# STM32F4.net
KiCad netlist of a schematic drawn in Altium Designer
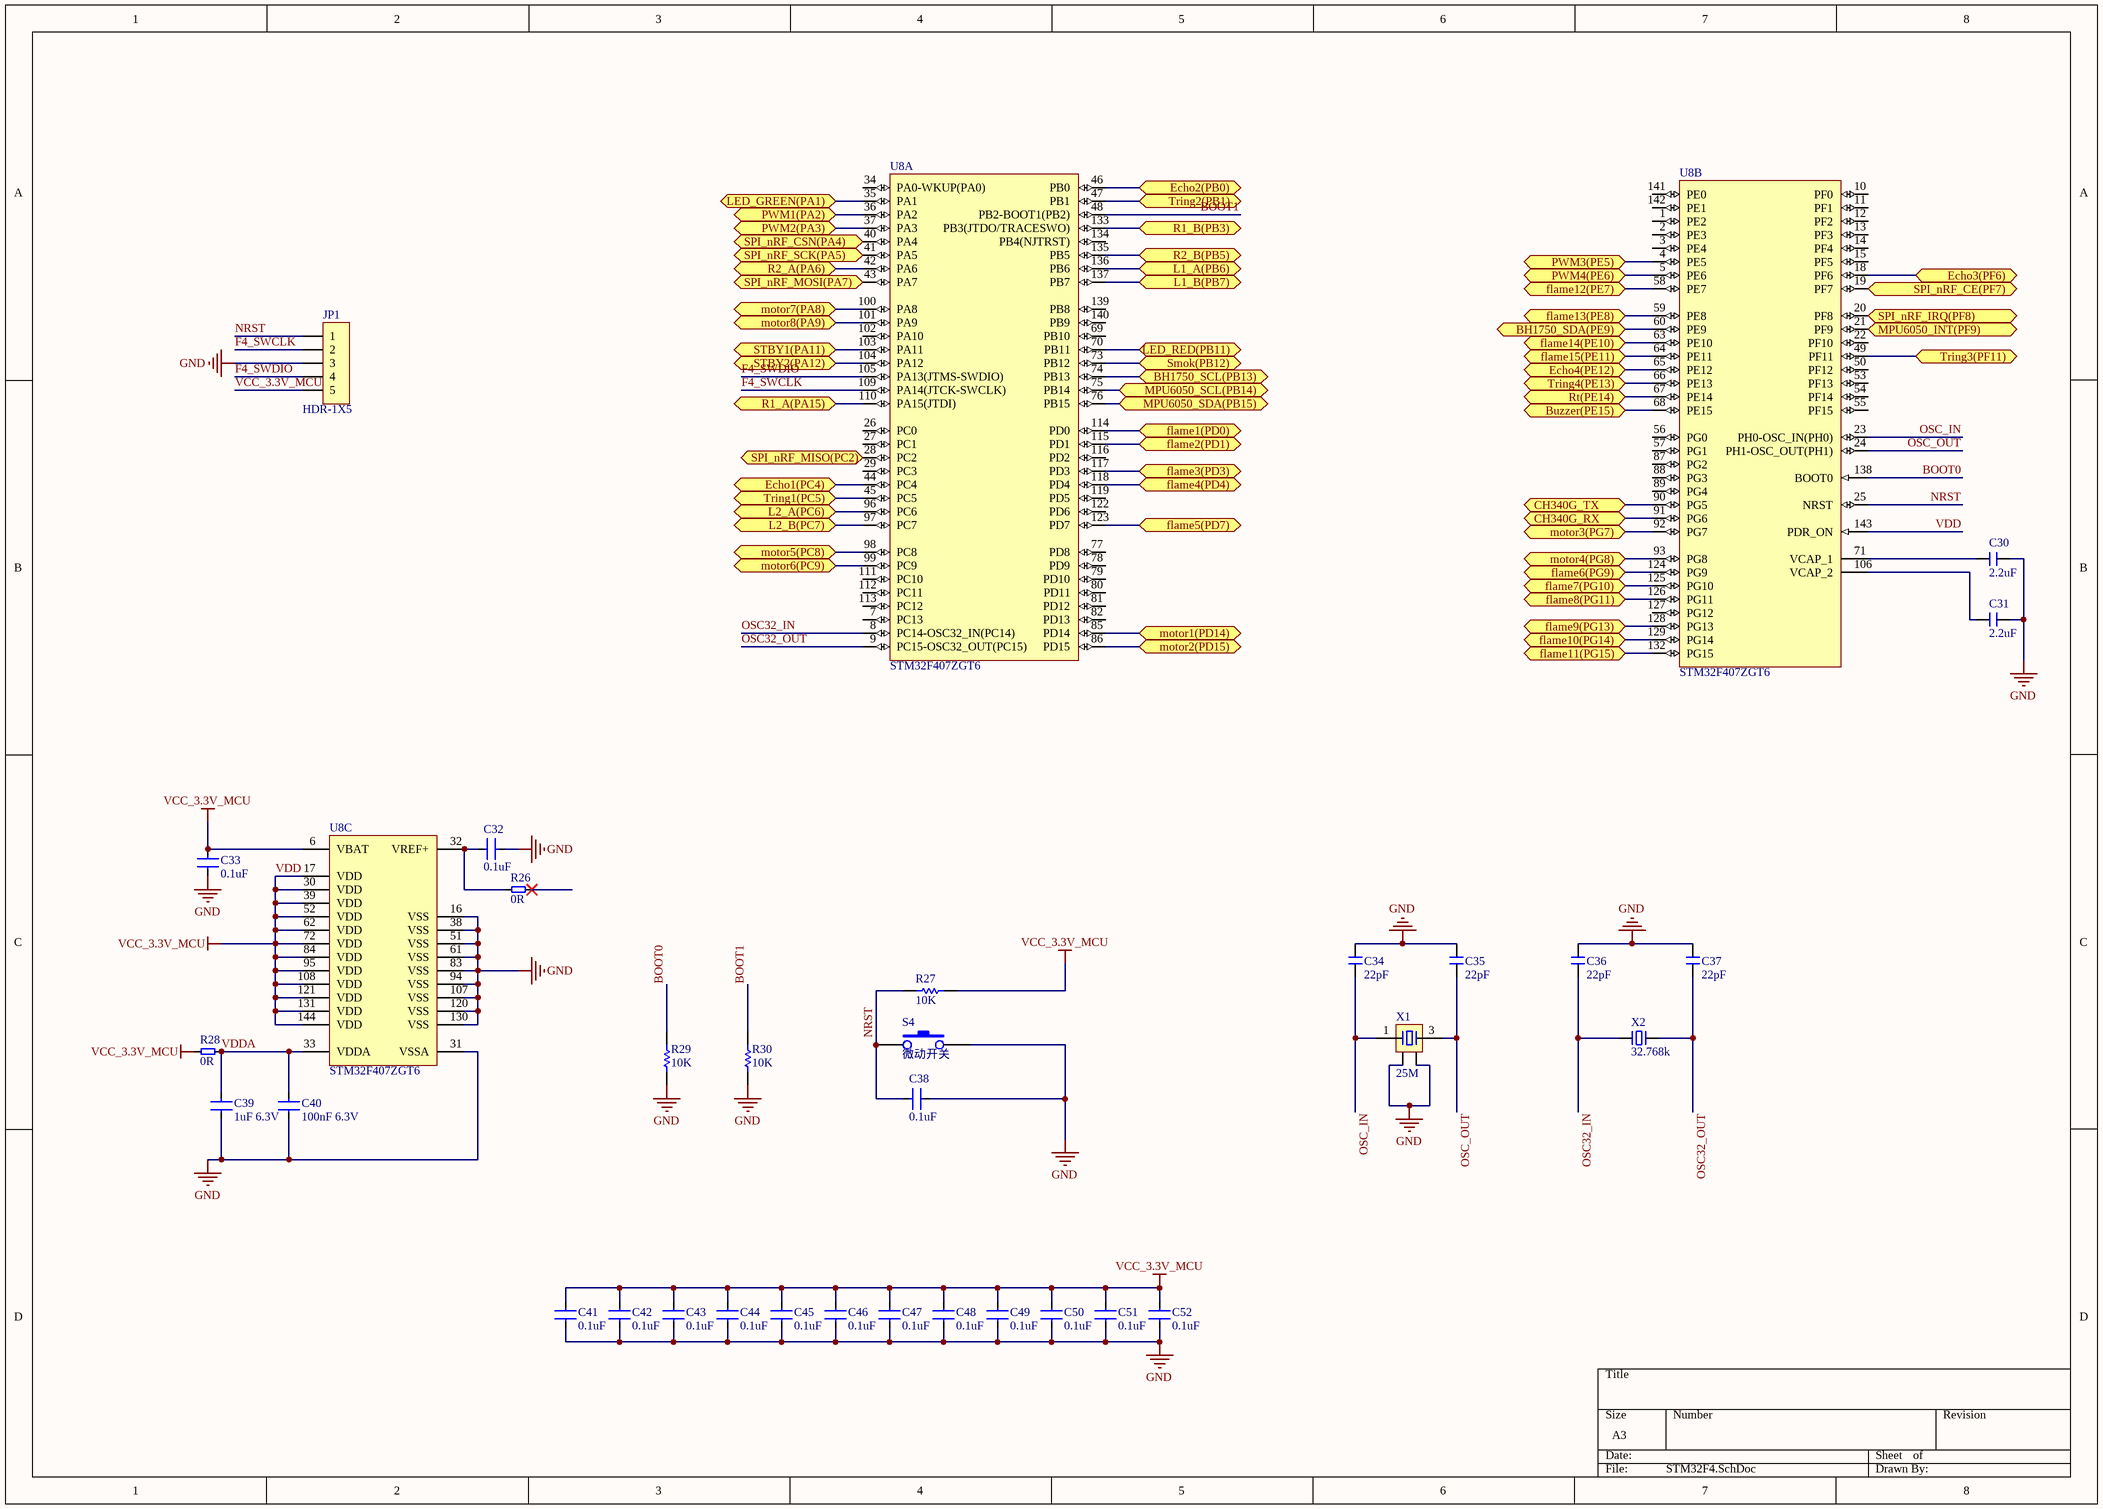
[diagram p0: STM32F4.SchDoc]

(export (version "E")
  (design (tool "Eeschema 10.0.6"))
  (components
    (comp (ref "C30")
      (value "2.2uF")
      (footprint "0603_C")
      (description "无极性贴片电容")
      (libsource (lib "3.1   - 电阻-电容-电感") (part "C"))
    )
    (comp (ref "C31")
      (value "2.2uF")
      (footprint "0603_C")
      (description "无极性贴片电容")
      (libsource (lib "3.1   - 电阻-电容-电感") (part "C"))
    )
    (comp (ref "C32") (value "0.1uF") (footprint "0603_C") (libsource (lib "电容") (part "C0805")))
    (comp (ref "C33") (value "0.1uF") (footprint "0603_C") (libsource (lib "电容") (part "C0805")))
    (comp (ref "C34")
      (value "22pF")
      (footprint "0603_C")
      (description "无极性贴片电容")
      (libsource (lib "3.1   - 电阻-电容-电感") (part "C"))
    )
    (comp (ref "C35")
      (value "22pF")
      (footprint "0603_C")
      (description "无极性贴片电容")
      (libsource (lib "3.1   - 电阻-电容-电感") (part "C"))
    )
    (comp (ref "C36")
      (value "22pF")
      (footprint "0603_C")
      (description "无极性贴片电容")
      (libsource (lib "3.1   - 电阻-电容-电感") (part "C"))
    )
    (comp (ref "C37")
      (value "22pF")
      (footprint "0603_C")
      (description "无极性贴片电容")
      (libsource (lib "3.1   - 电阻-电容-电感") (part "C"))
    )
    (comp (ref "C38") (value "0.1uF") (footprint "0603_C") (libsource (lib "电容") (part "C0805")))
    (comp (ref "C39") (value "1uF 6.3V") (footprint "0603_C") (libsource (lib "电容") (part "C0805")))
    (comp (ref "C40") (value "100nF 6.3V") (footprint "0603_C") (libsource (lib "电容") (part "C0805")))
    (comp (ref "C41") (value "0.1uF") (footprint "0603_C") (libsource (lib "电容") (part "C0805")))
    (comp (ref "C42") (value "0.1uF") (footprint "0603_C") (libsource (lib "电容") (part "C0805")))
    (comp (ref "C43") (value "0.1uF") (footprint "0603_C") (libsource (lib "电容") (part "C0805")))
    (comp (ref "C44") (value "0.1uF") (footprint "0603_C") (libsource (lib "电容") (part "C0805")))
    (comp (ref "C45") (value "0.1uF") (footprint "0603_C") (libsource (lib "电容") (part "C0805")))
    (comp (ref "C46") (value "0.1uF") (footprint "0603_C") (libsource (lib "电容") (part "C0805")))
    (comp (ref "C47") (value "0.1uF") (footprint "0603_C") (libsource (lib "电容") (part "C0805")))
    (comp (ref "C48") (value "0.1uF") (footprint "0603_C") (libsource (lib "电容") (part "C0805")))
    (comp (ref "C49") (value "0.1uF") (footprint "0603_C") (libsource (lib "电容") (part "C0805")))
    (comp (ref "C50") (value "0.1uF") (footprint "0603_C") (libsource (lib "电容") (part "C0805")))
    (comp (ref "C51") (value "0.1uF") (footprint "0603_C") (libsource (lib "电容") (part "C0805")))
    (comp (ref "C52") (value "0.1uF") (footprint "0603_C") (libsource (lib "电容") (part "C0805")))
    (comp (ref "JP1")
      (value "HDR-1X5")
      (footprint "XH2.54-WI-5P")
      (description "5P接插件")
      (libsource (lib "4.5   - 接插件-脚距2.54") (part "Header 5"))
    )
    (comp (ref "R26") (value "0R") (footprint "0603_L") (libsource (lib "电阻") (part "R0805")))
    (comp (ref "R27")
      (value "10K")
      (footprint "0603_R")
      (description "Resistor")
      (libsource (lib "Miscellaneous Devices") (part "Res1"))
    )
    (comp (ref "R28") (value "0R") (footprint "0603_L") (libsource (lib "电阻") (part "R0805")))
    (comp (ref "R29")
      (value "10K")
      (footprint "0603_R")
      (description "Resistor")
      (libsource (lib "Miscellaneous Devices") (part "Res1"))
    )
    (comp (ref "R30")
      (value "10K")
      (footprint "0603_R")
      (description "Resistor")
      (libsource (lib "Miscellaneous Devices") (part "Res1"))
    )
    (comp (ref "S4") (value "微动开关") (footprint "微动开关-1") (libsource (lib "开关") (part "微动开关")))
    (comp (ref "U8")
      (value "STM32F407ZGT6")
      (footprint "STM-LQFP144_N")
      (fields (field (name "MANUFACTURER") "STMicroelectronics"))
      (libsource (lib "STMicroelectronics STM32 F4") (part "STM32F407ZGT6"))
    )
    (comp (ref "X1")
      (value "25M")
      (footprint "SMD-3225_4P")
      (description "4脚无源晶振")
      (libsource (lib "10.1 - 保险丝-晶振") (part "XTAL-4P"))
    )
    (comp (ref "X2")
      (value "32.768k")
      (footprint "SMD-3215_2P FC - 135")
      (description "2脚无源脚晶振")
      (libsource (lib "10.1 - 保险丝-晶振") (part "XTAL-2P"))
    )
  )
  (nets
    (net (code "1") (name "/BH1750_SCL(PB13)") (class "Default")
      (node (ref "U8") (pin "74") (pinfunction "PB13_74") (pintype "bidirectional"))
    )
    (net (code "2") (name "/BH1750_SDA(PE9)") (class "Default")
      (node (ref "U8") (pin "60") (pinfunction "PE9_60") (pintype "bidirectional"))
    )
    (net (code "3") (name "/BOOT0") (class "Default")
      (node (ref "R29") (pin "1") (pinfunction "1_1") (pintype "passive"))
      (node (ref "U8") (pin "138") (pinfunction "BOOT0_138") (pintype "input"))
    )
    (net (code "4") (name "/BOOT1") (class "Default")
      (node (ref "R30") (pin "1") (pinfunction "1_1") (pintype "passive"))
      (node (ref "U8") (pin "48") (pinfunction "PB2-BOOT1(PB2)_48") (pintype "bidirectional"))
    )
    (net (code "5") (name "/Buzzer(PE15)") (class "Default")
      (node (ref "U8") (pin "68") (pinfunction "PE15_68") (pintype "bidirectional"))
    )
    (net (code "6") (name "/CH340G_RX") (class "Default")
      (node (ref "U8") (pin "91") (pinfunction "PG6_91") (pintype "bidirectional"))
    )
    (net (code "7") (name "/CH340G_TX") (class "Default")
      (node (ref "U8") (pin "90") (pinfunction "PG5_90") (pintype "bidirectional"))
    )
    (net (code "8") (name "/Echo1(PC4)") (class "Default")
      (node (ref "U8") (pin "44") (pinfunction "PC4_44") (pintype "bidirectional"))
    )
    (net (code "9") (name "/Echo2(PB0)") (class "Default")
      (node (ref "U8") (pin "46") (pinfunction "PB0_46") (pintype "bidirectional"))
    )
    (net (code "10") (name "/Echo3(PF6)") (class "Default")
      (node (ref "U8") (pin "18") (pinfunction "PF6_18") (pintype "bidirectional"))
    )
    (net (code "11") (name "/Echo4(PE12)") (class "Default")
      (node (ref "U8") (pin "65") (pinfunction "PE12_65") (pintype "bidirectional"))
    )
    (net (code "12") (name "/F4_SWCLK") (class "Default")
      (node (ref "JP1") (pin "2") (pinfunction "2_2") (pintype "passive"))
      (node (ref "U8") (pin "109") (pinfunction "PA14(JTCK-SWCLK)_109") (pintype "bidirectional"))
    )
    (net (code "13") (name "/F4_SWDIO") (class "Default")
      (node (ref "JP1") (pin "4") (pinfunction "4_4") (pintype "passive"))
      (node (ref "U8") (pin "105") (pinfunction "PA13(JTMS-SWDIO)_105") (pintype "bidirectional"))
    )
    (net (code "14") (name "/L1_A(PB6)") (class "Default")
      (node (ref "U8") (pin "136") (pinfunction "PB6_136") (pintype "bidirectional"))
    )
    (net (code "15") (name "/L1_B(PB7)") (class "Default")
      (node (ref "U8") (pin "137") (pinfunction "PB7_137") (pintype "bidirectional"))
    )
    (net (code "16") (name "/L2_A(PC6)") (class "Default")
      (node (ref "U8") (pin "96") (pinfunction "PC6_96") (pintype "bidirectional"))
    )
    (net (code "17") (name "/L2_B(PC7)") (class "Default")
      (node (ref "U8") (pin "97") (pinfunction "PC7_97") (pintype "bidirectional"))
    )
    (net (code "18") (name "/LED_GREEN(PA1)") (class "Default")
      (node (ref "U8") (pin "35") (pinfunction "PA1_35") (pintype "bidirectional"))
    )
    (net (code "19") (name "/LED_RED(PB11)") (class "Default")
      (node (ref "U8") (pin "70") (pinfunction "PB11_70") (pintype "bidirectional"))
    )
    (net (code "20") (name "/MPU6050_INT(PF9)") (class "Default")
      (node (ref "U8") (pin "21") (pinfunction "PF9_21") (pintype "bidirectional"))
    )
    (net (code "21") (name "/MPU6050_SCL(PB14)") (class "Default")
      (node (ref "U8") (pin "75") (pinfunction "PB14_75") (pintype "bidirectional"))
    )
    (net (code "22") (name "/MPU6050_SDA(PB15)") (class "Default")
      (node (ref "U8") (pin "76") (pinfunction "PB15_76") (pintype "bidirectional"))
    )
    (net (code "23") (name "/NRST") (class "Default")
      (node (ref "C38") (pin "1") (pinfunction "1_1") (pintype "passive"))
      (node (ref "JP1") (pin "1") (pinfunction "1_1") (pintype "passive"))
      (node (ref "R27") (pin "1") (pinfunction "1_1") (pintype "passive"))
      (node (ref "S4") (pin "1") (pinfunction "1_1") (pintype "passive"))
      (node (ref "U8") (pin "25") (pinfunction "NRST_25") (pintype "bidirectional"))
    )
    (net (code "24") (name "/OSC32_IN") (class "Default")
      (node (ref "C36") (pin "2") (pinfunction "2_2") (pintype "passive"))
      (node (ref "U8") (pin "8") (pinfunction "PC14-OSC32_IN(PC14)_8") (pintype "bidirectional"))
      (node (ref "X2") (pin "1") (pinfunction "1_1") (pintype "passive"))
    )
    (net (code "25") (name "/OSC32_OUT") (class "Default")
      (node (ref "C37") (pin "2") (pinfunction "2_2") (pintype "passive"))
      (node (ref "U8") (pin "9") (pinfunction "PC15-OSC32_OUT(PC15)_9") (pintype "bidirectional"))
      (node (ref "X2") (pin "2") (pinfunction "2_2") (pintype "passive"))
    )
    (net (code "26") (name "/OSC_IN") (class "Default")
      (node (ref "C34") (pin "2") (pinfunction "2_2") (pintype "passive"))
      (node (ref "U8") (pin "23") (pinfunction "PH0-OSC_IN(PH0)_23") (pintype "bidirectional"))
      (node (ref "X1") (pin "1") (pinfunction "1_1") (pintype "passive"))
    )
    (net (code "27") (name "/OSC_OUT") (class "Default")
      (node (ref "C35") (pin "2") (pinfunction "2_2") (pintype "passive"))
      (node (ref "U8") (pin "24") (pinfunction "PH1-OSC_OUT(PH1)_24") (pintype "bidirectional"))
      (node (ref "X1") (pin "3") (pinfunction "3_3") (pintype "passive"))
    )
    (net (code "28") (name "/PWM1(PA2)") (class "Default")
      (node (ref "U8") (pin "36") (pinfunction "PA2_36") (pintype "bidirectional"))
    )
    (net (code "29") (name "/PWM2(PA3)") (class "Default")
      (node (ref "U8") (pin "37") (pinfunction "PA3_37") (pintype "bidirectional"))
    )
    (net (code "30") (name "/PWM3(PE5)") (class "Default")
      (node (ref "U8") (pin "4") (pinfunction "PE5_4") (pintype "bidirectional"))
    )
    (net (code "31") (name "/PWM4(PE6)") (class "Default")
      (node (ref "U8") (pin "5") (pinfunction "PE6_5") (pintype "bidirectional"))
    )
    (net (code "32") (name "/R1_A(PA15)") (class "Default")
      (node (ref "U8") (pin "110") (pinfunction "PA15(JTDI)_110") (pintype "bidirectional"))
    )
    (net (code "33") (name "/R1_B(PB3)") (class "Default")
      (node (ref "U8") (pin "133") (pinfunction "PB3(JTDO/TRACESWO)_133") (pintype "bidirectional"))
    )
    (net (code "34") (name "/R2_A(PA6)") (class "Default")
      (node (ref "U8") (pin "42") (pinfunction "PA6_42") (pintype "bidirectional"))
    )
    (net (code "35") (name "/R2_B(PB5)") (class "Default")
      (node (ref "U8") (pin "135") (pinfunction "PB5_135") (pintype "bidirectional"))
    )
    (net (code "36") (name "/Rt(PE14)") (class "Default")
      (node (ref "U8") (pin "67") (pinfunction "PE14_67") (pintype "bidirectional"))
    )
    (net (code "37") (name "/SPI_nRF_CE(PF7)") (class "Default")
      (node (ref "U8") (pin "19") (pinfunction "PF7_19") (pintype "bidirectional"))
    )
    (net (code "38") (name "/SPI_nRF_CSN(PA4)") (class "Default")
      (node (ref "U8") (pin "40") (pinfunction "PA4_40") (pintype "bidirectional"))
    )
    (net (code "39") (name "/SPI_nRF_IRQ(PF8)") (class "Default")
      (node (ref "U8") (pin "20") (pinfunction "PF8_20") (pintype "bidirectional"))
    )
    (net (code "40") (name "/SPI_nRF_MISO(PC2)") (class "Default")
      (node (ref "U8") (pin "28") (pinfunction "PC2_28") (pintype "bidirectional"))
    )
    (net (code "41") (name "/SPI_nRF_MOSI(PA7)") (class "Default")
      (node (ref "U8") (pin "43") (pinfunction "PA7_43") (pintype "bidirectional"))
    )
    (net (code "42") (name "/SPI_nRF_SCK(PA5)") (class "Default")
      (node (ref "U8") (pin "41") (pinfunction "PA5_41") (pintype "bidirectional"))
    )
    (net (code "43") (name "/STBY1(PA11)") (class "Default")
      (node (ref "U8") (pin "103") (pinfunction "PA11_103") (pintype "bidirectional"))
    )
    (net (code "44") (name "/STBY2(PA12)") (class "Default")
      (node (ref "U8") (pin "104") (pinfunction "PA12_104") (pintype "bidirectional"))
    )
    (net (code "45") (name "/Smok(PB12)") (class "Default")
      (node (ref "U8") (pin "73") (pinfunction "PB12_73") (pintype "bidirectional"))
    )
    (net (code "46") (name "/Tring1(PC5)") (class "Default")
      (node (ref "U8") (pin "45") (pinfunction "PC5_45") (pintype "bidirectional"))
    )
    (net (code "47") (name "/Tring2(PB1)") (class "Default")
      (node (ref "U8") (pin "47") (pinfunction "PB1_47") (pintype "bidirectional"))
    )
    (net (code "48") (name "/Tring3(PF11)") (class "Default")
      (node (ref "U8") (pin "49") (pinfunction "PF11_49") (pintype "bidirectional"))
    )
    (net (code "49") (name "/Tring4(PE13)") (class "Default")
      (node (ref "U8") (pin "66") (pinfunction "PE13_66") (pintype "bidirectional"))
    )
    (net (code "50") (name "/VDDA") (class "Default")
      (node (ref "C39") (pin "1") (pinfunction "1_1") (pintype "passive"))
      (node (ref "C40") (pin "1") (pinfunction "1_1") (pintype "passive"))
      (node (ref "R28") (pin "2") (pinfunction "2_2") (pintype "passive"))
      (node (ref "U8") (pin "33") (pinfunction "VDDA_33") (pintype "power_in"))
    )
    (net (code "51") (name "/flame1(PD0)") (class "Default")
      (node (ref "U8") (pin "114") (pinfunction "PD0_114") (pintype "bidirectional"))
    )
    (net (code "52") (name "/flame2(PD1)") (class "Default")
      (node (ref "U8") (pin "115") (pinfunction "PD1_115") (pintype "bidirectional"))
    )
    (net (code "53") (name "/flame3(PD3)") (class "Default")
      (node (ref "U8") (pin "117") (pinfunction "PD3_117") (pintype "bidirectional"))
    )
    (net (code "54") (name "/flame4(PD4)") (class "Default")
      (node (ref "U8") (pin "118") (pinfunction "PD4_118") (pintype "bidirectional"))
    )
    (net (code "55") (name "/flame5(PD7)") (class "Default")
      (node (ref "U8") (pin "123") (pinfunction "PD7_123") (pintype "bidirectional"))
    )
    (net (code "56") (name "/flame6(PG9)") (class "Default")
      (node (ref "U8") (pin "124") (pinfunction "PG9_124") (pintype "bidirectional"))
    )
    (net (code "57") (name "/flame7(PG10)") (class "Default")
      (node (ref "U8") (pin "125") (pinfunction "PG10_125") (pintype "bidirectional"))
    )
    (net (code "58") (name "/flame8(PG11)") (class "Default")
      (node (ref "U8") (pin "126") (pinfunction "PG11_126") (pintype "bidirectional"))
    )
    (net (code "59") (name "/flame9(PG13)") (class "Default")
      (node (ref "U8") (pin "128") (pinfunction "PG13_128") (pintype "bidirectional"))
    )
    (net (code "60") (name "/flame10(PG14)") (class "Default")
      (node (ref "U8") (pin "129") (pinfunction "PG14_129") (pintype "bidirectional"))
    )
    (net (code "61") (name "/flame11(PG15)") (class "Default")
      (node (ref "U8") (pin "132") (pinfunction "PG15_132") (pintype "bidirectional"))
    )
    (net (code "62") (name "/flame12(PE7)") (class "Default")
      (node (ref "U8") (pin "58") (pinfunction "PE7_58") (pintype "bidirectional"))
    )
    (net (code "63") (name "/flame13(PE8)") (class "Default")
      (node (ref "U8") (pin "59") (pinfunction "PE8_59") (pintype "bidirectional"))
    )
    (net (code "64") (name "/flame14(PE10)") (class "Default")
      (node (ref "U8") (pin "63") (pinfunction "PE10_63") (pintype "bidirectional"))
    )
    (net (code "65") (name "/flame15(PE11)") (class "Default")
      (node (ref "U8") (pin "64") (pinfunction "PE11_64") (pintype "bidirectional"))
    )
    (net (code "66") (name "/motor1(PD14)") (class "Default")
      (node (ref "U8") (pin "85") (pinfunction "PD14_85") (pintype "bidirectional"))
    )
    (net (code "67") (name "/motor2(PD15)") (class "Default")
      (node (ref "U8") (pin "86") (pinfunction "PD15_86") (pintype "bidirectional"))
    )
    (net (code "68") (name "/motor3(PG7)") (class "Default")
      (node (ref "U8") (pin "92") (pinfunction "PG7_92") (pintype "bidirectional"))
    )
    (net (code "69") (name "/motor4(PG8)") (class "Default")
      (node (ref "U8") (pin "93") (pinfunction "PG8_93") (pintype "bidirectional"))
    )
    (net (code "70") (name "/motor5(PC8)") (class "Default")
      (node (ref "U8") (pin "98") (pinfunction "PC8_98") (pintype "bidirectional"))
    )
    (net (code "71") (name "/motor6(PC9)") (class "Default")
      (node (ref "U8") (pin "99") (pinfunction "PC9_99") (pintype "bidirectional"))
    )
    (net (code "72") (name "/motor7(PA8)") (class "Default")
      (node (ref "U8") (pin "100") (pinfunction "PA8_100") (pintype "bidirectional"))
    )
    (net (code "73") (name "/motor8(PA9)") (class "Default")
      (node (ref "U8") (pin "101") (pinfunction "PA9_101") (pintype "bidirectional"))
    )
    (net (code "74") (name "GND") (class "Default")
      (node (ref "C30") (pin "2") (pinfunction "2_2") (pintype "passive"))
      (node (ref "C31") (pin "1") (pinfunction "1_1") (pintype "passive"))
      (node (ref "C32") (pin "2") (pinfunction "2_2") (pintype "passive"))
      (node (ref "C33") (pin "1") (pinfunction "1_1") (pintype "passive"))
      (node (ref "C34") (pin "1") (pinfunction "1_1") (pintype "passive"))
      (node (ref "C35") (pin "1") (pinfunction "1_1") (pintype "passive"))
      (node (ref "C36") (pin "1") (pinfunction "1_1") (pintype "passive"))
      (node (ref "C37") (pin "1") (pinfunction "1_1") (pintype "passive"))
      (node (ref "C38") (pin "2") (pinfunction "2_2") (pintype "passive"))
      (node (ref "C39") (pin "2") (pinfunction "2_2") (pintype "passive"))
      (node (ref "C40") (pin "2") (pinfunction "2_2") (pintype "passive"))
      (node (ref "C41") (pin "1") (pinfunction "1_1") (pintype "passive"))
      (node (ref "C42") (pin "1") (pinfunction "1_1") (pintype "passive"))
      (node (ref "C43") (pin "1") (pinfunction "1_1") (pintype "passive"))
      (node (ref "C44") (pin "1") (pinfunction "1_1") (pintype "passive"))
      (node (ref "C45") (pin "1") (pinfunction "1_1") (pintype "passive"))
      (node (ref "C46") (pin "1") (pinfunction "1_1") (pintype "passive"))
      (node (ref "C47") (pin "1") (pinfunction "1_1") (pintype "passive"))
      (node (ref "C48") (pin "1") (pinfunction "1_1") (pintype "passive"))
      (node (ref "C49") (pin "1") (pinfunction "1_1") (pintype "passive"))
      (node (ref "C50") (pin "1") (pinfunction "1_1") (pintype "passive"))
      (node (ref "C51") (pin "1") (pinfunction "1_1") (pintype "passive"))
      (node (ref "C52") (pin "1") (pinfunction "1_1") (pintype "passive"))
      (node (ref "JP1") (pin "3") (pinfunction "3_3") (pintype "passive"))
      (node (ref "R29") (pin "2") (pinfunction "2_2") (pintype "passive"))
      (node (ref "R30") (pin "2") (pinfunction "2_2") (pintype "passive"))
      (node (ref "S4") (pin "2") (pinfunction "2_2") (pintype "passive"))
      (node (ref "U8") (pin "107") (pinfunction "VSS_107") (pintype "power_in"))
      (node (ref "U8") (pin "120") (pinfunction "VSS_120") (pintype "power_in"))
      (node (ref "U8") (pin "130") (pinfunction "VSS_130") (pintype "power_in"))
      (node (ref "U8") (pin "16") (pinfunction "VSS_16") (pintype "power_in"))
      (node (ref "U8") (pin "31") (pinfunction "VSSA_31") (pintype "power_in"))
      (node (ref "U8") (pin "38") (pinfunction "VSS_38") (pintype "power_in"))
      (node (ref "U8") (pin "51") (pinfunction "VSS_51") (pintype "power_in"))
      (node (ref "U8") (pin "61") (pinfunction "VSS_61") (pintype "power_in"))
      (node (ref "U8") (pin "83") (pinfunction "VSS_83") (pintype "power_in"))
      (node (ref "U8") (pin "94") (pinfunction "VSS_94") (pintype "power_in"))
      (node (ref "X1") (pin "2") (pinfunction "2_2") (pintype "passive"))
      (node (ref "X1") (pin "4") (pinfunction "4_4") (pintype "passive"))
    )
    (net (code "75") (name "Net-(U8B-VCAP_1)") (class "Default")
      (node (ref "C30") (pin "1") (pinfunction "1_1") (pintype "passive"))
      (node (ref "U8") (pin "71") (pinfunction "VCAP_1_71") (pintype "power_in"))
    )
    (net (code "76") (name "Net-(U8B-VCAP_2)") (class "Default")
      (node (ref "C31") (pin "2") (pinfunction "2_2") (pintype "passive"))
      (node (ref "U8") (pin "106") (pinfunction "VCAP_2_106") (pintype "power_in"))
    )
    (net (code "77") (name "Net-(U8C-VREF+)") (class "Default")
      (node (ref "C32") (pin "1") (pinfunction "1_1") (pintype "passive"))
      (node (ref "R26") (pin "1") (pinfunction "1_1") (pintype "passive"))
      (node (ref "U8") (pin "32") (pinfunction "VREF+_32") (pintype "power_in"))
    )
    (net (code "78") (name "VCC_3.3V_MCU") (class "Default")
      (node (ref "C33") (pin "2") (pinfunction "2_2") (pintype "passive"))
      (node (ref "C41") (pin "2") (pinfunction "2_2") (pintype "passive"))
      (node (ref "C42") (pin "2") (pinfunction "2_2") (pintype "passive"))
      (node (ref "C43") (pin "2") (pinfunction "2_2") (pintype "passive"))
      (node (ref "C44") (pin "2") (pinfunction "2_2") (pintype "passive"))
      (node (ref "C45") (pin "2") (pinfunction "2_2") (pintype "passive"))
      (node (ref "C46") (pin "2") (pinfunction "2_2") (pintype "passive"))
      (node (ref "C47") (pin "2") (pinfunction "2_2") (pintype "passive"))
      (node (ref "C48") (pin "2") (pinfunction "2_2") (pintype "passive"))
      (node (ref "C49") (pin "2") (pinfunction "2_2") (pintype "passive"))
      (node (ref "C50") (pin "2") (pinfunction "2_2") (pintype "passive"))
      (node (ref "C51") (pin "2") (pinfunction "2_2") (pintype "passive"))
      (node (ref "C52") (pin "2") (pinfunction "2_2") (pintype "passive"))
      (node (ref "JP1") (pin "5") (pinfunction "5_5") (pintype "passive"))
      (node (ref "R27") (pin "2") (pinfunction "2_2") (pintype "passive"))
      (node (ref "R28") (pin "1") (pinfunction "1_1") (pintype "passive"))
      (node (ref "U8") (pin "108") (pinfunction "VDD_108") (pintype "power_in"))
      (node (ref "U8") (pin "121") (pinfunction "VDD_121") (pintype "power_in"))
      (node (ref "U8") (pin "131") (pinfunction "VDD_131") (pintype "power_in"))
      (node (ref "U8") (pin "143") (pinfunction "PDR_ON_143") (pintype "input"))
      (node (ref "U8") (pin "144") (pinfunction "VDD_144") (pintype "power_in"))
      (node (ref "U8") (pin "17") (pinfunction "VDD_17") (pintype "power_in"))
      (node (ref "U8") (pin "30") (pinfunction "VDD_30") (pintype "power_in"))
      (node (ref "U8") (pin "39") (pinfunction "VDD_39") (pintype "power_in"))
      (node (ref "U8") (pin "52") (pinfunction "VDD_52") (pintype "power_in"))
      (node (ref "U8") (pin "6") (pinfunction "VBAT_6") (pintype "power_in"))
      (node (ref "U8") (pin "62") (pinfunction "VDD_62") (pintype "power_in"))
      (node (ref "U8") (pin "72") (pinfunction "VDD_72") (pintype "power_in"))
      (node (ref "U8") (pin "84") (pinfunction "VDD_84") (pintype "power_in"))
      (node (ref "U8") (pin "95") (pinfunction "VDD_95") (pintype "power_in"))
    )
    (net (code "79") (name "unconnected-(R26-Pad2)") (class "Default")
      (node (ref "R26") (pin "2") (pinfunction "2_2") (pintype "passive+no_connect"))
    )
    (net (code "80") (name "unconnected-(U8A-PA0-WKUP(PA0)-Pad34)") (class "Default")
      (node (ref "U8") (pin "34") (pinfunction "PA0-WKUP(PA0)_34") (pintype "bidirectional"))
    )
    (net (code "81") (name "unconnected-(U8A-PA10-Pad102)") (class "Default")
      (node (ref "U8") (pin "102") (pinfunction "PA10_102") (pintype "bidirectional"))
    )
    (net (code "82") (name "unconnected-(U8A-PB4(NJTRST)-Pad134)") (class "Default")
      (node (ref "U8") (pin "134") (pinfunction "PB4(NJTRST)_134") (pintype "bidirectional"))
    )
    (net (code "83") (name "unconnected-(U8A-PB8-Pad139)") (class "Default")
      (node (ref "U8") (pin "139") (pinfunction "PB8_139") (pintype "bidirectional"))
    )
    (net (code "84") (name "unconnected-(U8A-PB9-Pad140)") (class "Default")
      (node (ref "U8") (pin "140") (pinfunction "PB9_140") (pintype "bidirectional"))
    )
    (net (code "85") (name "unconnected-(U8A-PB10-Pad69)") (class "Default")
      (node (ref "U8") (pin "69") (pinfunction "PB10_69") (pintype "bidirectional"))
    )
    (net (code "86") (name "unconnected-(U8A-PC0-Pad26)") (class "Default")
      (node (ref "U8") (pin "26") (pinfunction "PC0_26") (pintype "bidirectional"))
    )
    (net (code "87") (name "unconnected-(U8A-PC1-Pad27)") (class "Default")
      (node (ref "U8") (pin "27") (pinfunction "PC1_27") (pintype "bidirectional"))
    )
    (net (code "88") (name "unconnected-(U8A-PC3-Pad29)") (class "Default")
      (node (ref "U8") (pin "29") (pinfunction "PC3_29") (pintype "bidirectional"))
    )
    (net (code "89") (name "unconnected-(U8A-PC10-Pad111)") (class "Default")
      (node (ref "U8") (pin "111") (pinfunction "PC10_111") (pintype "bidirectional"))
    )
    (net (code "90") (name "unconnected-(U8A-PC11-Pad112)") (class "Default")
      (node (ref "U8") (pin "112") (pinfunction "PC11_112") (pintype "bidirectional"))
    )
    (net (code "91") (name "unconnected-(U8A-PC12-Pad113)") (class "Default")
      (node (ref "U8") (pin "113") (pinfunction "PC12_113") (pintype "bidirectional"))
    )
    (net (code "92") (name "unconnected-(U8A-PC13-Pad7)") (class "Default")
      (node (ref "U8") (pin "7") (pinfunction "PC13_7") (pintype "bidirectional"))
    )
    (net (code "93") (name "unconnected-(U8A-PD2-Pad116)") (class "Default")
      (node (ref "U8") (pin "116") (pinfunction "PD2_116") (pintype "bidirectional"))
    )
    (net (code "94") (name "unconnected-(U8A-PD5-Pad119)") (class "Default")
      (node (ref "U8") (pin "119") (pinfunction "PD5_119") (pintype "bidirectional"))
    )
    (net (code "95") (name "unconnected-(U8A-PD6-Pad122)") (class "Default")
      (node (ref "U8") (pin "122") (pinfunction "PD6_122") (pintype "bidirectional"))
    )
    (net (code "96") (name "unconnected-(U8A-PD8-Pad77)") (class "Default")
      (node (ref "U8") (pin "77") (pinfunction "PD8_77") (pintype "bidirectional"))
    )
    (net (code "97") (name "unconnected-(U8A-PD9-Pad78)") (class "Default")
      (node (ref "U8") (pin "78") (pinfunction "PD9_78") (pintype "bidirectional"))
    )
    (net (code "98") (name "unconnected-(U8A-PD10-Pad79)") (class "Default")
      (node (ref "U8") (pin "79") (pinfunction "PD10_79") (pintype "bidirectional"))
    )
    (net (code "99") (name "unconnected-(U8A-PD11-Pad80)") (class "Default")
      (node (ref "U8") (pin "80") (pinfunction "PD11_80") (pintype "bidirectional"))
    )
    (net (code "100") (name "unconnected-(U8A-PD12-Pad81)") (class "Default")
      (node (ref "U8") (pin "81") (pinfunction "PD12_81") (pintype "bidirectional"))
    )
    (net (code "101") (name "unconnected-(U8A-PD13-Pad82)") (class "Default")
      (node (ref "U8") (pin "82") (pinfunction "PD13_82") (pintype "bidirectional"))
    )
    (net (code "102") (name "unconnected-(U8B-PE0-Pad141)") (class "Default")
      (node (ref "U8") (pin "141") (pinfunction "PE0_141") (pintype "bidirectional"))
    )
    (net (code "103") (name "unconnected-(U8B-PE1-Pad142)") (class "Default")
      (node (ref "U8") (pin "142") (pinfunction "PE1_142") (pintype "bidirectional"))
    )
    (net (code "104") (name "unconnected-(U8B-PE2-Pad1)") (class "Default")
      (node (ref "U8") (pin "1") (pinfunction "PE2_1") (pintype "bidirectional"))
    )
    (net (code "105") (name "unconnected-(U8B-PE3-Pad2)") (class "Default")
      (node (ref "U8") (pin "2") (pinfunction "PE3_2") (pintype "bidirectional"))
    )
    (net (code "106") (name "unconnected-(U8B-PE4-Pad3)") (class "Default")
      (node (ref "U8") (pin "3") (pinfunction "PE4_3") (pintype "bidirectional"))
    )
    (net (code "107") (name "unconnected-(U8B-PF0-Pad10)") (class "Default")
      (node (ref "U8") (pin "10") (pinfunction "PF0_10") (pintype "bidirectional"))
    )
    (net (code "108") (name "unconnected-(U8B-PF1-Pad11)") (class "Default")
      (node (ref "U8") (pin "11") (pinfunction "PF1_11") (pintype "bidirectional"))
    )
    (net (code "109") (name "unconnected-(U8B-PF2-Pad12)") (class "Default")
      (node (ref "U8") (pin "12") (pinfunction "PF2_12") (pintype "bidirectional"))
    )
    (net (code "110") (name "unconnected-(U8B-PF3-Pad13)") (class "Default")
      (node (ref "U8") (pin "13") (pinfunction "PF3_13") (pintype "bidirectional"))
    )
    (net (code "111") (name "unconnected-(U8B-PF4-Pad14)") (class "Default")
      (node (ref "U8") (pin "14") (pinfunction "PF4_14") (pintype "bidirectional"))
    )
    (net (code "112") (name "unconnected-(U8B-PF5-Pad15)") (class "Default")
      (node (ref "U8") (pin "15") (pinfunction "PF5_15") (pintype "bidirectional"))
    )
    (net (code "113") (name "unconnected-(U8B-PF10-Pad22)") (class "Default")
      (node (ref "U8") (pin "22") (pinfunction "PF10_22") (pintype "bidirectional"))
    )
    (net (code "114") (name "unconnected-(U8B-PF12-Pad50)") (class "Default")
      (node (ref "U8") (pin "50") (pinfunction "PF12_50") (pintype "bidirectional"))
    )
    (net (code "115") (name "unconnected-(U8B-PF13-Pad53)") (class "Default")
      (node (ref "U8") (pin "53") (pinfunction "PF13_53") (pintype "bidirectional"))
    )
    (net (code "116") (name "unconnected-(U8B-PF14-Pad54)") (class "Default")
      (node (ref "U8") (pin "54") (pinfunction "PF14_54") (pintype "bidirectional"))
    )
    (net (code "117") (name "unconnected-(U8B-PF15-Pad55)") (class "Default")
      (node (ref "U8") (pin "55") (pinfunction "PF15_55") (pintype "bidirectional"))
    )
    (net (code "118") (name "unconnected-(U8B-PG0-Pad56)") (class "Default")
      (node (ref "U8") (pin "56") (pinfunction "PG0_56") (pintype "bidirectional"))
    )
    (net (code "119") (name "unconnected-(U8B-PG1-Pad57)") (class "Default")
      (node (ref "U8") (pin "57") (pinfunction "PG1_57") (pintype "bidirectional"))
    )
    (net (code "120") (name "unconnected-(U8B-PG2-Pad87)") (class "Default")
      (node (ref "U8") (pin "87") (pinfunction "PG2_87") (pintype "bidirectional"))
    )
    (net (code "121") (name "unconnected-(U8B-PG3-Pad88)") (class "Default")
      (node (ref "U8") (pin "88") (pinfunction "PG3_88") (pintype "bidirectional"))
    )
    (net (code "122") (name "unconnected-(U8B-PG4-Pad89)") (class "Default")
      (node (ref "U8") (pin "89") (pinfunction "PG4_89") (pintype "bidirectional"))
    )
    (net (code "123") (name "unconnected-(U8B-PG12-Pad127)") (class "Default")
      (node (ref "U8") (pin "127") (pinfunction "PG12_127") (pintype "bidirectional"))
    )
  )
)
